# CH2-Input.net
KiCad netlist of a schematic drawn in Altium Designer
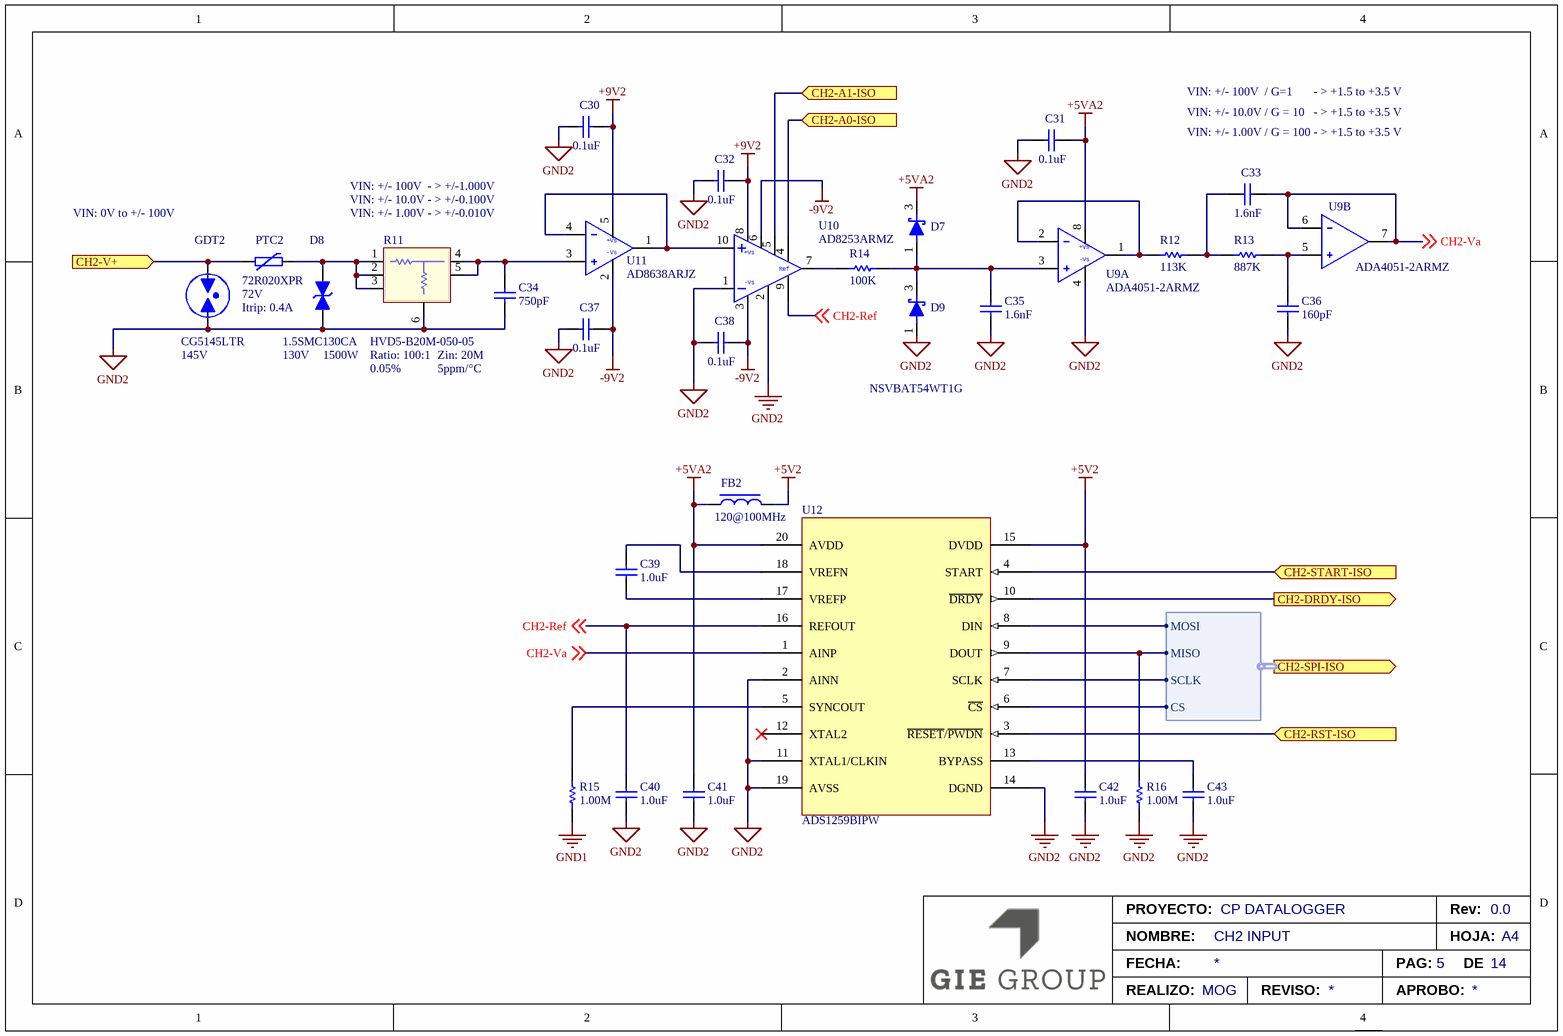
[diagram p0: CH2-Input.SchDoc]

(export (version "E")
  (design (tool "Eeschema 10.0.6"))
  (components
    (comp (ref "C30")
      (value "0.1uF")
      (footprint "CAP-0603")
      (description "CAP CER 0.1uF 50V X7R 0603")
      (fields (field (name "PARTNUMBER") "C0603C104K5RACAUTO") (field (name "MANUFACTURER") "Kemet"))
      (libsource (lib "Kemet") (part "C0603C104K5RACAUTO"))
    )
    (comp (ref "C31")
      (value "0.1uF")
      (footprint "CAP-0603")
      (description "CAP CER 0.1uF 50V X7R 0603")
      (fields (field (name "PARTNUMBER") "C0603C104K5RACAUTO") (field (name "MANUFACTURER") "Kemet"))
      (libsource (lib "Kemet") (part "C0603C104K5RACAUTO"))
    )
    (comp (ref "C32")
      (value "0.1uF")
      (footprint "CAP-0603")
      (description "CAP CER 0.1uF 50V X7R 0603")
      (fields (field (name "PARTNUMBER") "C0603C104K5RACAUTO") (field (name "MANUFACTURER") "Kemet"))
      (libsource (lib "Kemet") (part "C0603C104K5RACAUTO"))
    )
    (comp (ref "C33")
      (value "1.6nF")
      (footprint "CAP-0603")
      (description "CAP CER 1600´pF 50V C0G 0603")
      (fields (field (name "PARTNUMBER") "C0603C162J5GAC7867") (field (name "MANUFACTURER") "Kemet"))
      (libsource (lib "Kemet") (part "C0603C162J5GAC7867"))
    )
    (comp (ref "C34")
      (value "750pF")
      (footprint "CAP-0603")
      (description "CAP CER 750´pF 50V C0G 0603")
      (fields (field (name "PARTNUMBER") "C0603C161J1GAC7867") (field (name "MANUFACTURER") "Kemet"))
      (libsource (lib "Kemet") (part "C0603C751J5GAC7867"))
    )
    (comp (ref "C35")
      (value "1.6nF")
      (footprint "CAP-0603")
      (description "CAP CER 1600´pF 50V C0G 0603")
      (fields (field (name "PARTNUMBER") "C0603C162J5GAC7867") (field (name "MANUFACTURER") "Kemet"))
      (libsource (lib "Kemet") (part "C0603C162J5GAC7867"))
    )
    (comp (ref "C36")
      (value "160pF")
      (footprint "CAP-0603")
      (description "CAP CER 160 pF 100V C0G 0603")
      (fields (field (name "PARTNUMBER") "C0603C161J1GAC7867") (field (name "MANUFACTURER") "Kemet"))
      (libsource (lib "Kemet") (part "C0603C161J1GAC7867"))
    )
    (comp (ref "C37")
      (value "0.1uF")
      (footprint "CAP-0603")
      (description "CAP CER 0.1uF 50V X7R 0603")
      (fields (field (name "PARTNUMBER") "C0603C104K5RACAUTO") (field (name "MANUFACTURER") "Kemet"))
      (libsource (lib "Kemet") (part "C0603C104K5RACAUTO"))
    )
    (comp (ref "C38")
      (value "0.1uF")
      (footprint "CAP-0603")
      (description "CAP CER 0.1uF 50V X7R 0603")
      (fields (field (name "PARTNUMBER") "C0603C104K5RACAUTO") (field (name "MANUFACTURER") "Kemet"))
      (libsource (lib "Kemet") (part "C0603C104K5RACAUTO"))
    )
    (comp (ref "C39")
      (value "1.0uF")
      (footprint "CAP-0603")
      (description "CAP CER 1uF 25V X7R 0603")
      (fields (field (name "PARTNUMBER") "C0603C105M3RAC7867") (field (name "MANUFACTURER") "Kemet"))
      (libsource (lib "Kemet") (part "C0603C105M3RAC7867"))
    )
    (comp (ref "C40")
      (value "1.0uF")
      (footprint "CAP-0603")
      (description "CAP CER 1uF 25V X7R 0603")
      (fields (field (name "PARTNUMBER") "C0603C105M3RAC7867") (field (name "MANUFACTURER") "Kemet"))
      (libsource (lib "Kemet") (part "C0603C105M3RAC7867"))
    )
    (comp (ref "C41")
      (value "1.0uF")
      (footprint "CAP-0603")
      (description "CAP CER 1uF 25V X7R 0603")
      (fields (field (name "PARTNUMBER") "C0603C105M3RAC7867") (field (name "MANUFACTURER") "Kemet"))
      (libsource (lib "Kemet") (part "C0603C105M3RAC7867"))
    )
    (comp (ref "C42")
      (value "1.0uF")
      (footprint "CAP-0603")
      (description "CAP CER 1uF 25V X7R 0603")
      (fields (field (name "PARTNUMBER") "C0603C105M3RAC7867") (field (name "MANUFACTURER") "Kemet"))
      (libsource (lib "Kemet") (part "C0603C105M3RAC7867"))
    )
    (comp (ref "C43")
      (value "1.0uF")
      (footprint "CAP-0603")
      (description "CAP CER 1uF 25V X7R 0603")
      (fields (field (name "PARTNUMBER") "C0603C105M3RAC7867") (field (name "MANUFACTURER") "Kemet"))
      (libsource (lib "Kemet") (part "C0603C105M3RAC7867"))
    )
    (comp (ref "D7")
      (value "NSVBAT54WT1G")
      (footprint "SOT-323-3")
      (description "Schottky Diode 30V 200mA SOT323")
      (fields (field (name "MANUFACTURER") "OnSemiconductor"))
      (libsource (lib "OnSemiconductors") (part "NSVBAT54WT1G"))
    )
    (comp (ref "D8")
      (value "1.5SMC130CA")
      (footprint "SMC - BIIDIR")
      (description "TVS Diode 1.5kW 130V 5% Bi-Directional")
      (fields
        (field (name "MANUFACTURER") "Littelfuse")
        (field (name "PARTNUMBER") "1.5SMC130CA")
        (field (name "VOLTAGE") "130V")
        (field (name "POWER") "1500W")
      )
      (libsource (lib "Littlelfuse") (part "1.5SMC130CA"))
    )
    (comp (ref "D9")
      (value "NSVBAT54WT1G")
      (footprint "SOT-323-3")
      (description "Schottky Diode 30V 200mA SOT323")
      (fields (field (name "MANUFACTURER") "OnSemiconductor") (field (name "PARTNUMBER") "NSVBAT54WT1G"))
      (libsource (lib "OnSemiconductors") (part "NSVBAT54WT1G"))
    )
    (comp (ref "FB2")
      (value "120@100MHz")
      (footprint "IND-0603")
      (description "Ferrite Bead 120Ohms 900mA 25% DCR=130m")
      (fields (field (name "MANUFACTURER") "Kemet") (field (name "PARTNUMBER") "Z0603C121GPWZT"))
      (libsource (lib "Kemet") (part "Z0603C121GPWZT"))
    )
    (comp (ref "GDT2")
      (value "CG5145LTR")
      (footprint "LITTLELFUSE-CG5XXXLTR")
      (description "Gas Discharge Tube 145V")
      (fields
        (field (name "MANUFACTURER") "Littelfuse")
        (field (name "PARTNUMBER") "CG5145LTR")
        (field (name "VOLTAGE") "145V")
      )
      (libsource (lib "Littlelfuse") (part "CG5145LTR"))
    )
    (comp (ref "PTC2")
      (value "72R020XPR")
      (footprint "LITTLELFUSE-72R020X")
      (description "PTC Polyfuse Radial 72V 0.2A")
      (fields
        (field (name "MANUFACTURER") "Littlelfuse")
        (field (name "PARTNUMBER") "72R020XPR")
        (field (name "VOLTAGE") "72V")
        (field (name "ITRIP") "0.4A")
      )
      (libsource (lib "Littlelfuse") (part "72R020XPR"))
    )
    (comp (ref "R11")
      (value "HVD5-B20M-050-05")
      (footprint "CADDOCK - HVD5-B20M-050-05")
      (description "20M ohm 0.05% 5ppm Voltage Divider")
      (fields
        (field (name "MANUFACTURER") "Caddock")
        (field (name "PARTNUMBER") "HVD5-B20M-050-05")
        (field (name "THERMAL") "5ppm/°C")
        (field (name "TOLERANCE") "0.05%")
        (field (name "RATIO") "100:1")
        (field (name "ZIN") "20M")
      )
      (libsource (lib "Caddock") (part "HVD5-B20M-050-05"))
    )
    (comp (ref "R12")
      (value "113K")
      (footprint "RES-0603")
      (description "RES SMD 113K OHM 1% 1/10W 0603")
      (fields (field (name "TOLERANCE") "1%") (field (name "MANUFACTURER") "Yageo"))
      (libsource (lib "Yageo") (part "RC0603FR-07113KL"))
    )
    (comp (ref "R13")
      (value "887K")
      (footprint "RES-0603")
      (description "RES SMD 887K OHM 1% 1/10W 0603")
      (fields (field (name "TOLERANCE") "1%") (field (name "MANUFACTURER") "Yageo"))
      (libsource (lib "Yageo") (part "RC0603FR-07887KL"))
    )
    (comp (ref "R14")
      (value "100K")
      (footprint "RES-0603")
      (description "RES SMD 100K OHM 1% 1/10W 0603")
      (fields (field (name "TOLERANCE") "1%") (field (name "MANUFACTURER") "Yageo"))
      (libsource (lib "Yageo") (part "RC0603FR-07100KL"))
    )
    (comp (ref "R15")
      (value "1.00M")
      (footprint "RES-0603")
      (description "RES SMD 1M OHM 1% 1/10W 0603")
      (fields (field (name "TOLERANCE") "1%") (field (name "MANUFACTURER") "Yageo"))
      (libsource (lib "Yageo") (part "RC0603FR-071ML"))
    )
    (comp (ref "R16")
      (value "1.00M")
      (footprint "RES-0603")
      (description "RES SMD 1M OHM 1% 1/10W 0603")
      (fields (field (name "TOLERANCE") "1%") (field (name "MANUFACTURER") "Yageo"))
      (libsource (lib "Yageo") (part "RC0603FR-071ML"))
    )
    (comp (ref "U9")
      (value "ADA4051-2ARMZ")
      (footprint "MSOP8")
      (description "Dual  Precision Amplifier Micro Power Auto Zero")
      (fields (field (name "MANUFACTURER") "Analog Devices") (field (name "PARTNUMBER") "ADA4051-2ARMZ"))
      (libsource (lib "AnalogDevices") (part "ADA4051-2ARMZ"))
    )
    (comp (ref "U10")
      (value "AD8253ARMZ")
      (footprint "MSOP10")
      (description "Instrumentation Amplifiers High Speed Programmable High Gain In-Amp")
      (fields (field (name "MANUFACTURER") "Analog Devices Inc"))
      (libsource (lib "AnalogDevices") (part "AD8253ARMZ"))
    )
    (comp (ref "U11")
      (value "AD8638ARJZ")
      (footprint "SOT23-5")
      (description "16V Auto-Zero CMOS Amplifier")
      (fields (field (name "MANUFACTURER") "Analog Devices") (field (name "PARTNUMBER") "AD8638ARJZ"))
      (libsource (lib "AnalogDevices") (part "AD8638ARJZ"))
    )
    (comp (ref "U12")
      (value "ADS1259BIPW")
      (footprint "TSSOP20")
      (description "Analog to Digital Converter 14.4kSPS 24-Bit")
      (fields (field (name "MANUFACTURER") "Texas Instruments") (field (name "PARTNUMBER") "ADS1259BIPW"))
      (libsource (lib "TexasInstruments") (part "ADS1259BIPW"))
    )
  )
  (nets
    (net (code "2") (name "+5V2") (class "Default")
      (node (ref "C42") (pin "2") (pinfunction "2_2") (pintype "passive"))
      (node (ref "FB2") (pin "2") (pinfunction "2_2") (pintype "passive"))
      (node (ref "U12") (pin "15") (pinfunction "DVDD_15") (pintype "power_in"))
    )
    (net (code "3") (name "+5VA2") (class "Default")
      (node (ref "C31") (pin "2") (pinfunction "2_2") (pintype "passive"))
      (node (ref "C41") (pin "2") (pinfunction "2_2") (pintype "passive"))
      (node (ref "D7") (pin "3") (pinfunction "K_3") (pintype "passive"))
      (node (ref "FB2") (pin "1") (pinfunction "1_1") (pintype "passive"))
      (node (ref "U12") (pin "20") (pinfunction "AVDD_20") (pintype "power_in"))
      (node (ref "U9") (pin "8") (pinfunction "+VS_8") (pintype "power_in"))
    )
    (net (code "4") (name "+9V2") (class "Default")
      (node (ref "C30") (pin "2") (pinfunction "2_2") (pintype "passive"))
      (node (ref "C32") (pin "2") (pinfunction "2_2") (pintype "passive"))
      (node (ref "U10") (pin "8") (pinfunction "+Vs_8") (pintype "passive"))
      (node (ref "U11") (pin "5") (pinfunction "+VS_5") (pintype "power_in"))
    )
    (net (code "5") (name "-9V2") (class "Default")
      (node (ref "C37") (pin "2") (pinfunction "2_2") (pintype "passive"))
      (node (ref "C38") (pin "2") (pinfunction "2_2") (pintype "passive"))
      (node (ref "U10") (pin "3") (pinfunction "-Vs_3") (pintype "passive"))
      (node (ref "U10") (pin "6") (pinfunction "WR_6") (pintype "passive"))
      (node (ref "U11") (pin "2") (pinfunction "-Vs_2") (pintype "power_in"))
    )
    (net (code "6") (name "/CH2-A0-ISO") (class "Default")
      (node (ref "U10") (pin "4") (pinfunction "A0_4") (pintype "passive"))
    )
    (net (code "7") (name "/CH2-A1-ISO") (class "Default")
      (node (ref "U10") (pin "5") (pinfunction "A1_5") (pintype "passive"))
    )
    (net (code "8") (name "/CH2-DRDY-ISO") (class "Default")
      (node (ref "U12") (pin "10") (pinfunction "~{DRDY}_10") (pintype "output"))
    )
    (net (code "9") (name "/CH2-RST-ISO") (class "Default")
      (node (ref "U12") (pin "3") (pinfunction "~{RESET}/~{PWDN}_3") (pintype "input"))
    )
    (net (code "10") (name "/CH2-START-ISO") (class "Default")
      (node (ref "U12") (pin "4") (pinfunction "START_4") (pintype "input"))
    )
    (net (code "11") (name "/CH2-V+") (class "Default")
      (node (ref "GDT2") (pin "1") (pinfunction "A_1") (pintype "passive"))
      (node (ref "PTC2") (pin "1") (pinfunction "1_1") (pintype "passive"))
    )
    (net (code "12") (name "/CS") (class "Default")
      (node (ref "U12") (pin "6") (pinfunction "~{CS}_6") (pintype "input"))
    )
    (net (code "13") (name "/MISO") (class "Default")
      (node (ref "R16") (pin "2") (pinfunction "2_2") (pintype "passive"))
      (node (ref "U12") (pin "9") (pinfunction "DOUT_9") (pintype "output"))
    )
    (net (code "14") (name "/MOSI") (class "Default")
      (node (ref "U12") (pin "8") (pinfunction "DIN_8") (pintype "input"))
    )
    (net (code "15") (name "/SCLK") (class "Default")
      (node (ref "U12") (pin "7") (pinfunction "SCLK_7") (pintype "input"))
    )
    (net (code "17") (name "CH2-Ref") (class "Default")
      (node (ref "C40") (pin "2") (pinfunction "2_2") (pintype "passive"))
      (node (ref "U10") (pin "9") (pinfunction "REF_9") (pintype "passive"))
      (node (ref "U12") (pin "16") (pinfunction "REFOUT_16") (pintype "power_in"))
    )
    (net (code "18") (name "CH2-Va") (class "Default")
      (node (ref "C33") (pin "1") (pinfunction "1_1") (pintype "passive"))
      (node (ref "U12") (pin "1") (pinfunction "AINP_1") (pintype "passive"))
      (node (ref "U9") (pin "6") (pinfunction "-INB_6") (pintype "passive"))
      (node (ref "U9") (pin "7") (pinfunction "OUTB_7") (pintype "passive"))
    )
    (net (code "19") (name "GND1") (class "Default")
      (node (ref "R15") (pin "1") (pinfunction "1_1") (pintype "passive"))
    )
    (net (code "20") (name "GND2") (class "Default")
      (node (ref "C30") (pin "1") (pinfunction "1_1") (pintype "passive"))
      (node (ref "C31") (pin "1") (pinfunction "1_1") (pintype "passive"))
      (node (ref "C32") (pin "1") (pinfunction "1_1") (pintype "passive"))
      (node (ref "C34") (pin "1") (pinfunction "1_1") (pintype "passive"))
      (node (ref "C35") (pin "1") (pinfunction "1_1") (pintype "passive"))
      (node (ref "C36") (pin "1") (pinfunction "1_1") (pintype "passive"))
      (node (ref "C37") (pin "1") (pinfunction "1_1") (pintype "passive"))
      (node (ref "C38") (pin "1") (pinfunction "1_1") (pintype "passive"))
      (node (ref "C40") (pin "1") (pinfunction "1_1") (pintype "passive"))
      (node (ref "C41") (pin "1") (pinfunction "1_1") (pintype "passive"))
      (node (ref "C42") (pin "1") (pinfunction "1_1") (pintype "passive"))
      (node (ref "C43") (pin "1") (pinfunction "1_1") (pintype "passive"))
      (node (ref "D8") (pin "2") (pinfunction "K_2") (pintype "passive"))
      (node (ref "D9") (pin "1") (pinfunction "A_1") (pintype "passive"))
      (node (ref "GDT2") (pin "2") (pinfunction "K_2") (pintype "passive"))
      (node (ref "R11") (pin "6") (pinfunction "6_6") (pintype "passive"))
      (node (ref "R16") (pin "1") (pinfunction "1_1") (pintype "passive"))
      (node (ref "U10") (pin "1") (pinfunction "-_IN_1") (pintype "passive"))
      (node (ref "U10") (pin "2") (pinfunction "DGND_2") (pintype "passive"))
      (node (ref "U12") (pin "11") (pinfunction "XTAL1/CLKIN_11") (pintype "power_in"))
      (node (ref "U12") (pin "14") (pinfunction "DGND_14") (pintype "power_in"))
      (node (ref "U12") (pin "19") (pinfunction "AVSS_19") (pintype "power_in"))
      (node (ref "U12") (pin "2") (pinfunction "AINN_2") (pintype "passive"))
      (node (ref "U9") (pin "4") (pinfunction "-Vs_4") (pintype "power_in"))
    )
    (net (code "21") (name "Net-(C33-Pad2)") (class "Default")
      (node (ref "C33") (pin "2") (pinfunction "2_2") (pintype "passive"))
      (node (ref "R12") (pin "2") (pinfunction "2_2") (pintype "passive"))
      (node (ref "R13") (pin "1") (pinfunction "1_1") (pintype "passive"))
    )
    (net (code "22") (name "Net-(D7-A)") (class "Default")
      (node (ref "C35") (pin "2") (pinfunction "2_2") (pintype "passive"))
      (node (ref "D7") (pin "1") (pinfunction "A_1") (pintype "passive"))
      (node (ref "D9") (pin "3") (pinfunction "K_3") (pintype "passive"))
      (node (ref "R14") (pin "2") (pinfunction "2_2") (pintype "passive"))
      (node (ref "U9") (pin "3") (pinfunction "+INA_3") (pintype "passive"))
    )
    (net (code "23") (name "Net-(D8-A)") (class "Default")
      (node (ref "D8") (pin "1") (pinfunction "A_1") (pintype "passive"))
      (node (ref "PTC2") (pin "2") (pinfunction "2_2") (pintype "passive"))
      (node (ref "R11") (pin "1") (pinfunction "1_1") (pintype "passive"))
      (node (ref "R11") (pin "2") (pinfunction "2_2") (pintype "passive"))
      (node (ref "R11") (pin "3") (pinfunction "3_3") (pintype "passive"))
    )
    (net (code "24") (name "Net-(U9A--INA)") (class "Default")
      (node (ref "R12") (pin "1") (pinfunction "1_1") (pintype "passive"))
      (node (ref "U9") (pin "1") (pinfunction "OUTA_1") (pintype "passive"))
      (node (ref "U9") (pin "2") (pinfunction "-INA_2") (pintype "passive"))
    )
    (net (code "25") (name "Net-(U9B-+INB)") (class "Default")
      (node (ref "C36") (pin "2") (pinfunction "2_2") (pintype "passive"))
      (node (ref "R13") (pin "2") (pinfunction "2_2") (pintype "passive"))
      (node (ref "U9") (pin "5") (pinfunction "+INB_5") (pintype "passive"))
    )
    (net (code "26") (name "Net-(U10-+_IN)") (class "Default")
      (node (ref "U10") (pin "10") (pinfunction "+_IN_10") (pintype "passive"))
      (node (ref "U11") (pin "1") (pinfunction "OUT_1") (pintype "passive"))
      (node (ref "U11") (pin "4") (pinfunction "-IN_4") (pintype "passive"))
    )
    (net (code "27") (name "Net-(U10-OUT)") (class "Default")
      (node (ref "R14") (pin "1") (pinfunction "1_1") (pintype "passive"))
      (node (ref "U10") (pin "7") (pinfunction "OUT_7") (pintype "passive"))
    )
    (net (code "28") (name "Net-(U11-+IN)") (class "Default")
      (node (ref "C34") (pin "2") (pinfunction "2_2") (pintype "passive"))
      (node (ref "R11") (pin "4") (pinfunction "4_4") (pintype "passive"))
      (node (ref "R11") (pin "5") (pinfunction "5_5") (pintype "passive"))
      (node (ref "U11") (pin "3") (pinfunction "+IN_3") (pintype "passive"))
    )
    (net (code "29") (name "Net-(U12-BYPASS)") (class "Default")
      (node (ref "C43") (pin "2") (pinfunction "2_2") (pintype "passive"))
      (node (ref "U12") (pin "13") (pinfunction "BYPASS_13") (pintype "power_in"))
    )
    (net (code "30") (name "Net-(U12-SYNCOUT)") (class "Default")
      (node (ref "R15") (pin "2") (pinfunction "2_2") (pintype "passive"))
      (node (ref "U12") (pin "5") (pinfunction "SYNCOUT_5") (pintype "passive"))
    )
    (net (code "31") (name "Net-(U12-VREFN)") (class "Default")
      (node (ref "C39") (pin "2") (pinfunction "2_2") (pintype "passive"))
      (node (ref "U12") (pin "18") (pinfunction "VREFN_18") (pintype "power_in"))
    )
    (net (code "32") (name "Net-(U12-VREFP)") (class "Default")
      (node (ref "C39") (pin "1") (pinfunction "1_1") (pintype "passive"))
      (node (ref "U12") (pin "17") (pinfunction "VREFP_17") (pintype "power_in"))
    )
    (net (code "33") (name "unconnected-(U12-XTAL2-Pad12)") (class "Default")
      (node (ref "U12") (pin "12") (pinfunction "XTAL2_12") (pintype "power_in+no_connect"))
    )
  )
)
